# project1.net
KiCad netlist of a schematic drawn in Altium Designer
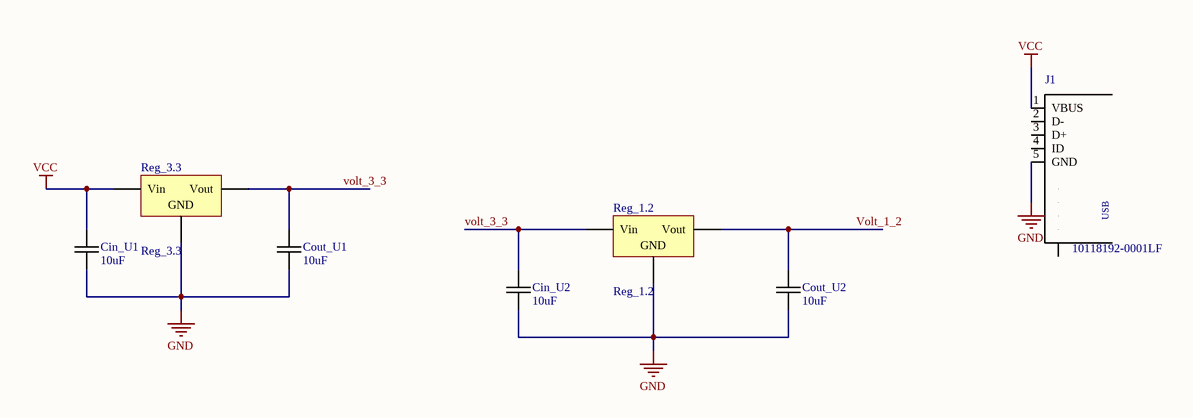
[diagram p0: project1.SchDoc]

(export (version "E")
  (design (tool "Eeschema 10.0.6"))
  (components
    (comp (ref "Cin_U1")
      (value "10uF")
      (footprint "0805C-GENERIC")
      (description "CAPACITOR 0805 CERAMIC")
      (fields
        (field (name "MANUFACTURER PART NUMBER") "C2012X5R1C106M")
        (field (name "MANUFACTURER") "TDK Corporation")
      )
      (libsource (lib "vh_altium_library") (part "0805C-10UF-16V-X5R-TDK"))
    )
    (comp (ref "Cin_U2")
      (value "10uF")
      (footprint "0805C-GENERIC")
      (description "CAPACITOR 0805 CERAMIC")
      (fields
        (field (name "MANUFACTURER PART NUMBER") "C2012X5R1C106M")
        (field (name "MANUFACTURER") "TDK Corporation")
      )
      (libsource (lib "vh_altium_library") (part "0805C-10UF-16V-X5R-TDK"))
    )
    (comp (ref "Cout_U1")
      (value "10uF")
      (footprint "0805C-GENERIC")
      (description "CAPACITOR 0805 CERAMIC")
      (fields
        (field (name "MANUFACTURER PART NUMBER") "C2012X5R1C106M")
        (field (name "MANUFACTURER") "TDK Corporation")
      )
      (libsource (lib "vh_altium_library") (part "0805C-10UF-16V-X5R-TDK"))
    )
    (comp (ref "Cout_U2")
      (value "10uF")
      (footprint "0805C-GENERIC")
      (description "CAPACITOR 0805 CERAMIC")
      (fields
        (field (name "MANUFACTURER PART NUMBER") "C2012X5R1C106M")
        (field (name "MANUFACTURER") "TDK Corporation")
      )
      (libsource (lib "vh_altium_library") (part "0805C-10UF-16V-X5R-TDK"))
    )
    (comp (ref "J1")
      (value "10118192-0001LF")
      (footprint "10118192-0001LF_10118192-0001LF(Primary)")
      (description "Conn Micro USB Type B RCP 5 POS 0.65mm Solder RA SMD 5 Terminal 1 Port T/R")
      (fields (field (name "MF") "Amphenol"))
      (libsource (lib "USB Micro Port") (part "10118192-0001LF"))
    )
    (comp (ref "Reg_1.2")
      (value "Reg_1.2")
      (footprint "D2PAK_N")
      (description "Voltage Regulator")
      (fields (field (name "PUBLISHER") "Altium Limited"))
      (libsource (lib "Miscellaneous Devices") (part "Volt Reg"))
    )
    (comp (ref "Reg_3.3")
      (value "Reg_3.3")
      (footprint "D2PAK_N")
      (description "Voltage Regulator")
      (fields (field (name "PUBLISHER") "Altium Limited"))
      (libsource (lib "Miscellaneous Devices") (part "Volt Reg"))
    )
  )
  (nets
    (net (code "1") (name "/Volt_1_2") (class "Default")
      (node (ref "Cout_U2") (pin "1") (pintype "passive"))
      (node (ref "Reg_1.2") (pin "3") (pinfunction "Vout_3") (pintype "passive"))
    )
    (net (code "2") (name "/volt_3_3") (class "Default")
      (node (ref "Cin_U2") (pin "1") (pintype "passive"))
      (node (ref "Cout_U1") (pin "1") (pintype "passive"))
      (node (ref "Reg_1.2") (pin "1") (pinfunction "Vin_1") (pintype "passive"))
      (node (ref "Reg_3.3") (pin "3") (pinfunction "Vout_3") (pintype "passive"))
    )
    (net (code "3") (name "GND") (class "Default")
      (node (ref "Cin_U1") (pin "2") (pintype "passive"))
      (node (ref "Cin_U2") (pin "2") (pintype "passive"))
      (node (ref "Cout_U1") (pin "2") (pintype "passive"))
      (node (ref "Cout_U2") (pin "2") (pintype "passive"))
      (node (ref "J1") (pin "5") (pinfunction "GND_5") (pintype "passive"))
      (node (ref "Reg_1.2") (pin "2") (pinfunction "GND_2") (pintype "passive"))
      (node (ref "Reg_3.3") (pin "2") (pinfunction "GND_2") (pintype "passive"))
    )
    (net (code "4") (name "VCC") (class "Default")
      (node (ref "Cin_U1") (pin "1") (pintype "passive"))
      (node (ref "J1") (pin "1") (pinfunction "VBUS_1") (pintype "passive"))
      (node (ref "Reg_3.3") (pin "1") (pinfunction "Vin_1") (pintype "passive"))
    )
    (net (code "5") (name "unconnected-(J1-D+-Pad3)") (class "Default")
      (node (ref "J1") (pin "3") (pinfunction "D+_3") (pintype "passive"))
    )
    (net (code "6") (name "unconnected-(J1-D--Pad2)") (class "Default")
      (node (ref "J1") (pin "2") (pinfunction "D-_2") (pintype "passive"))
    )
    (net (code "7") (name "unconnected-(J1-ID-Pad4)") (class "Default")
      (node (ref "J1") (pin "4") (pinfunction "ID_4") (pintype "passive"))
    )
    (net (code "8") (name "unconnected-(J1-S-PadM1)") (class "Default")
      (node (ref "J1") (pin "M1") (pinfunction "S_M1") (pintype "passive"))
    )
    (net (code "9") (name "unconnected-(J1-S-PadM2)") (class "Default")
      (node (ref "J1") (pin "M2") (pinfunction "S_M2") (pintype "passive"))
    )
    (net (code "10") (name "unconnected-(J1-S-PadS1)") (class "Default")
      (node (ref "J1") (pin "S1") (pinfunction "S_S1") (pintype "passive"))
    )
    (net (code "11") (name "unconnected-(J1-S-PadS2)") (class "Default")
      (node (ref "J1") (pin "S2") (pinfunction "S_S2") (pintype "passive"))
    )
    (net (code "12") (name "unconnected-(J1-S-PadS3)") (class "Default")
      (node (ref "J1") (pin "S3") (pinfunction "S_S3") (pintype "passive"))
    )
    (net (code "13") (name "unconnected-(J1-S-PadS4)") (class "Default")
      (node (ref "J1") (pin "S4") (pinfunction "S_S4") (pintype "passive"))
    )
  )
)
